# Solar_Charge_Controller.net
KiCad netlist of a schematic drawn in EAGLE
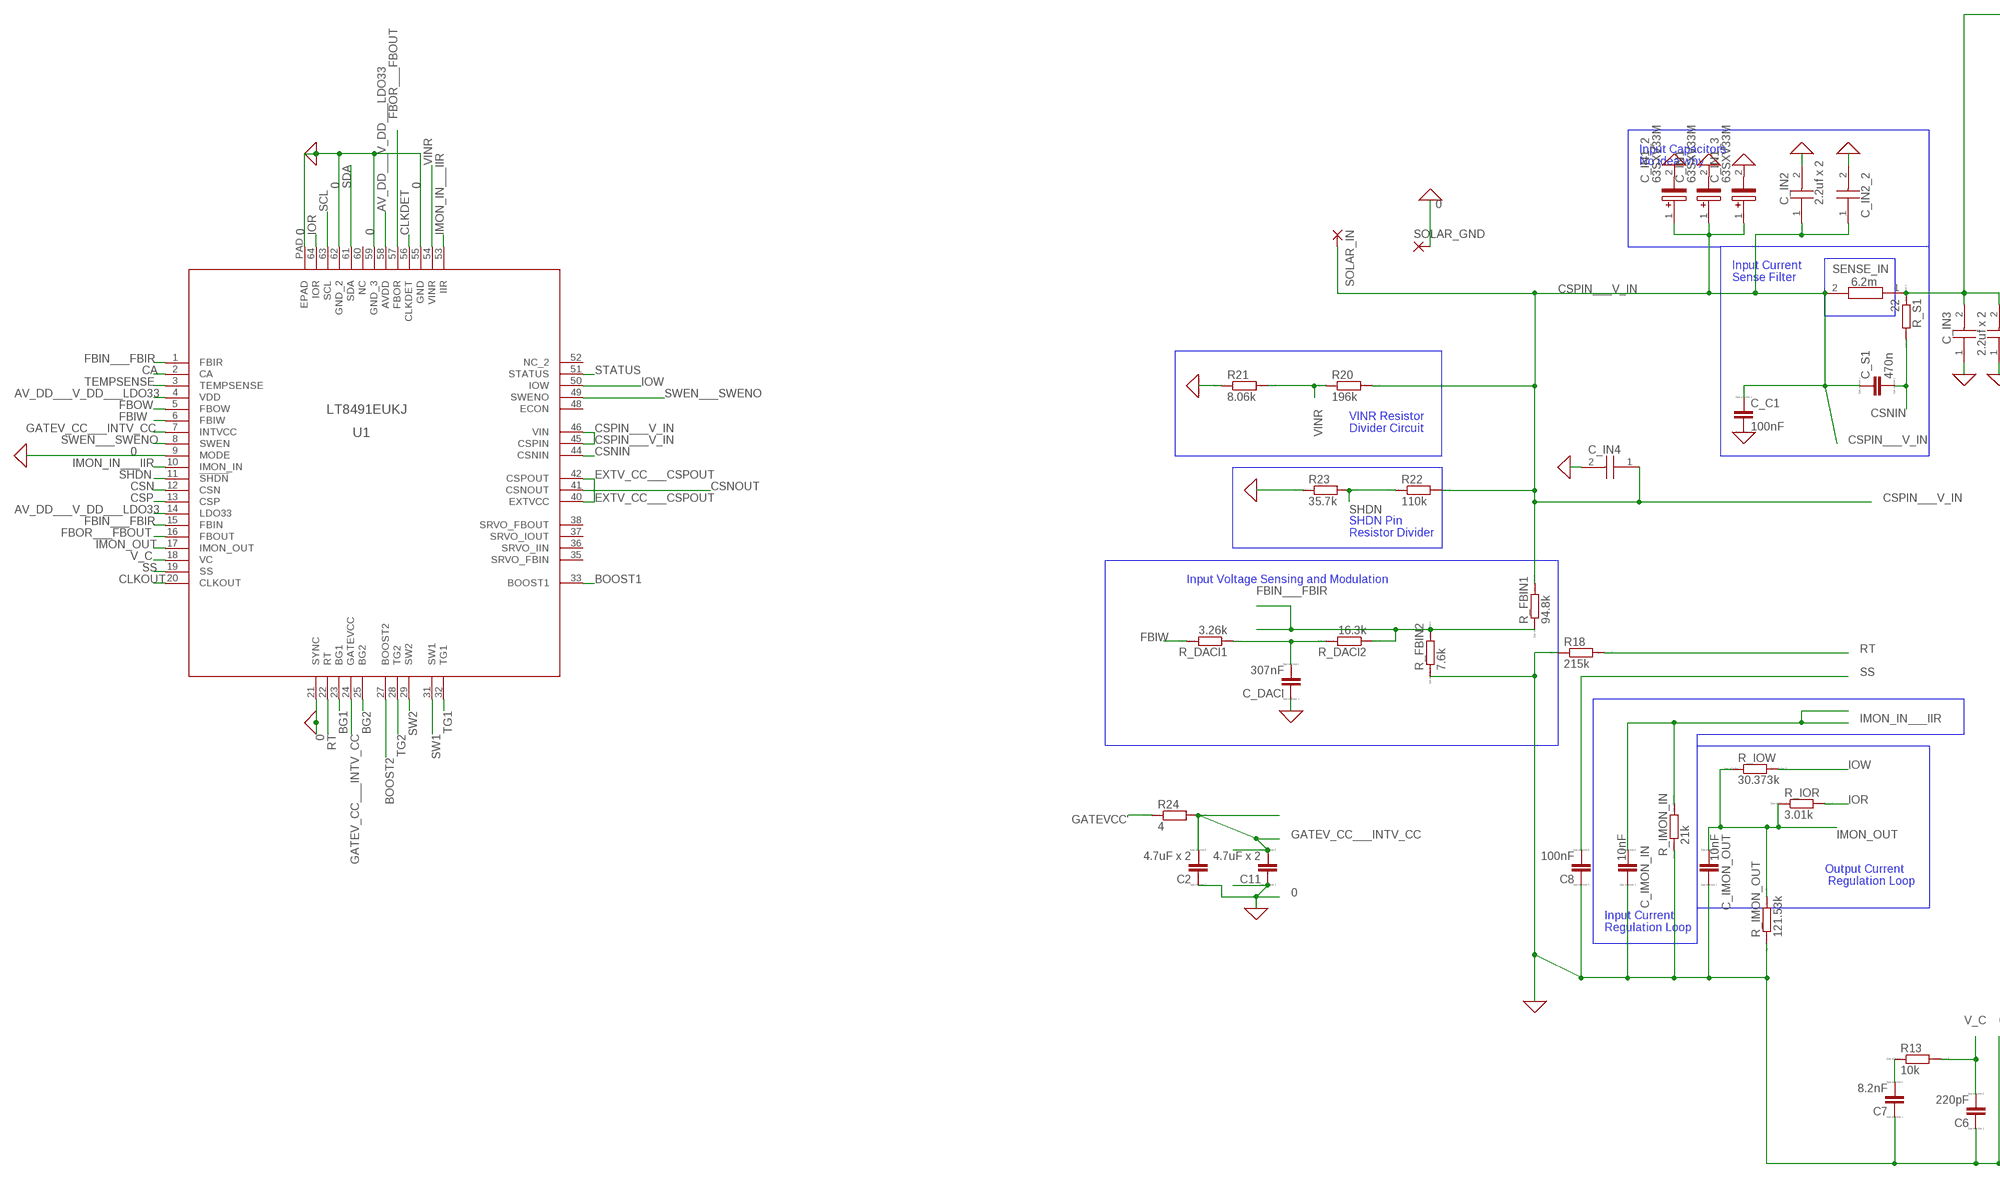
[diagram p0: schematic, sheet 1, part 1 of 2]
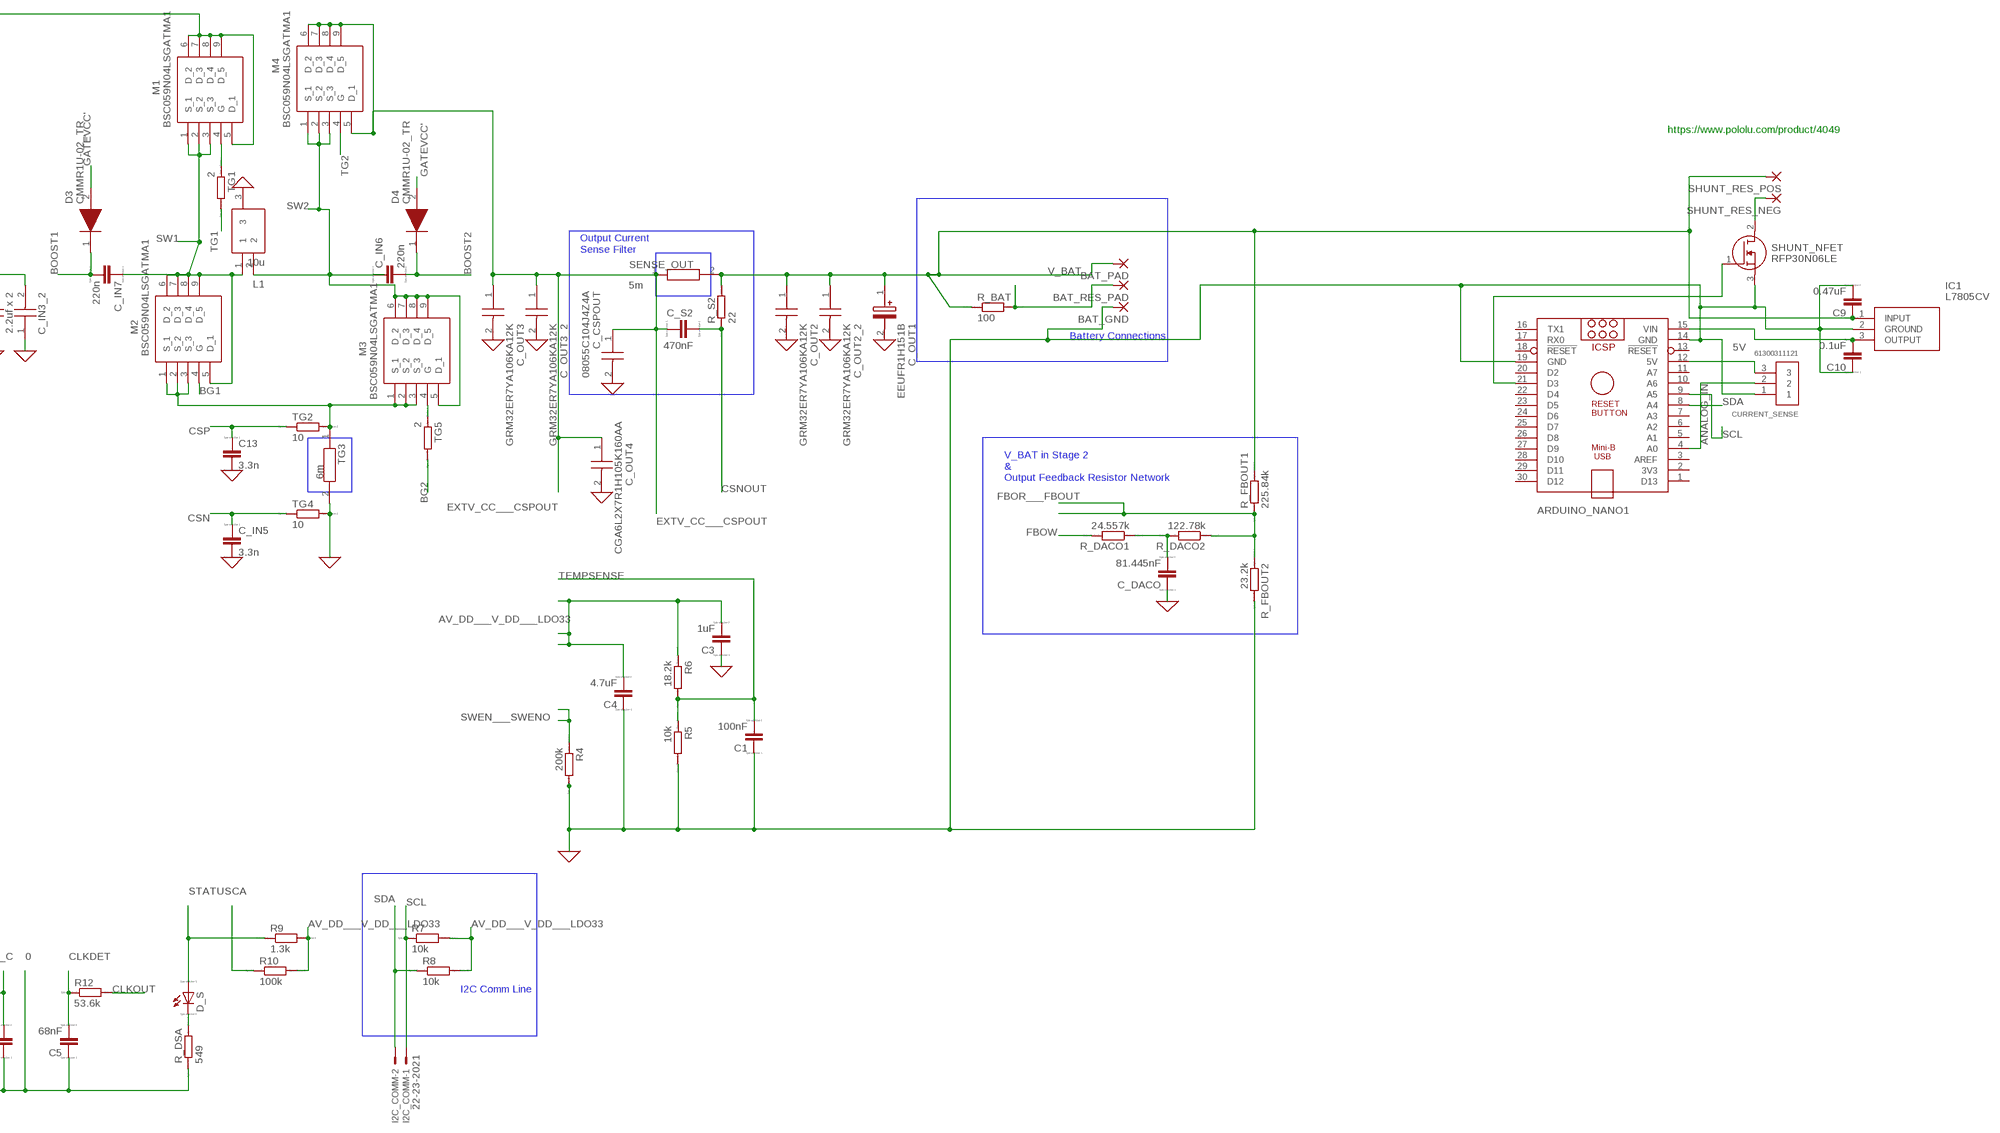
[diagram p1: schematic, sheet 1, part 2 of 2]

(export (version "E")
  (design (tool "Eeschema 10.0.6"))
  (components
    (comp (ref "ARDUINO_NANO1")
      (value "ARDUINO_NANO")
      (footprint "eagle-import:ARDUINO_NANO")
      (libsource (lib "eagle-import") (part "ARDUINO_NANO"))
    )
    (comp (ref "BAT_GND")
      (value "SMD5")
      (footprint "eagle-import:SMD2,54-5,08")
      (libsource (lib "eagle-import") (part "SMD5"))
    )
    (comp (ref "BAT_PAD")
      (value "SMD5")
      (footprint "eagle-import:SMD2,54-5,08")
      (libsource (lib "eagle-import") (part "SMD5"))
    )
    (comp (ref "BAT_RES_PAD")
      (value "SMD5")
      (footprint "eagle-import:SMD2,54-5,08")
      (libsource (lib "eagle-import") (part "SMD5"))
    )
    (comp (ref "C1")
      (value "100nF")
      (footprint "eagle-import:C1206")
      (libsource (lib "eagle-import") (part "CC1206"))
    )
    (comp (ref "C2")
      (value "4.7uF x 2")
      (footprint "eagle-import:C1206")
      (libsource (lib "eagle-import") (part "CC1206"))
    )
    (comp (ref "C3")
      (value "1uF")
      (footprint "eagle-import:C1206")
      (libsource (lib "eagle-import") (part "CC1206"))
    )
    (comp (ref "C4")
      (value "4.7uF")
      (footprint "eagle-import:C1206")
      (libsource (lib "eagle-import") (part "CC1206"))
    )
    (comp (ref "C5")
      (value "68nF")
      (footprint "eagle-import:C0603")
      (libsource (lib "eagle-import") (part "CC0603"))
    )
    (comp (ref "C6")
      (value "220pF")
      (footprint "eagle-import:C1206")
      (libsource (lib "eagle-import") (part "CC1206"))
    )
    (comp (ref "C7")
      (value "8.2nF")
      (footprint "eagle-import:C1206")
      (libsource (lib "eagle-import") (part "CC1206"))
    )
    (comp (ref "C8")
      (value "100nF")
      (footprint "eagle-import:C1206")
      (libsource (lib "eagle-import") (part "CC1206"))
    )
    (comp (ref "C9")
      (value "0.47uF")
      (footprint "eagle-import:C1206")
      (libsource (lib "eagle-import") (part "CC1206"))
    )
    (comp (ref "C10")
      (value "0.1uF")
      (footprint "eagle-import:C1206")
      (libsource (lib "eagle-import") (part "CC1206"))
    )
    (comp (ref "C11")
      (value "4.7uF x 2")
      (footprint "eagle-import:C1206")
      (libsource (lib "eagle-import") (part "CC1206"))
    )
    (comp (ref "C13")
      (value "3.3n")
      (footprint "eagle-import:C1206")
      (libsource (lib "eagle-import") (part "CC1206"))
    )
    (comp (ref "CURRENT_SENSE")
      (value "61300311121")
      (footprint "eagle-import:61300311121")
      (fields
        (field (name "DIGI_KEY_PART_NUMBER") "732-5316-ND")
        (field (name "MANUFACTURER") "Wurth Electronics Inc.")
        (field (name "CREATED_BY") "PCBLayout.com")
      )
      (libsource (lib "eagle-import") (part "61300311121"))
    )
    (comp (ref "C_C1")
      (value "100nF")
      (footprint "eagle-import:C1206")
      (libsource (lib "eagle-import") (part "CC1206"))
    )
    (comp (ref "C_CSPOUT")
      (value "08055C104J4Z4A")
      (footprint "eagle-import:CAPC2012X127N")
      (fields (field (name "MOUSER_PART_NUMBER") "581-08055C104J4Z4A"))
      (libsource (lib "eagle-import") (part "08055C104J4Z4A"))
    )
    (comp (ref "C_DACI")
      (value "307nF")
      (footprint "eagle-import:C1206")
      (libsource (lib "eagle-import") (part "CC1206"))
    )
    (comp (ref "C_DACO")
      (value "81.445nF")
      (footprint "eagle-import:C1206")
      (libsource (lib "eagle-import") (part "CC1206"))
    )
    (comp (ref "C_IMON_IN")
      (value "10nF")
      (footprint "eagle-import:C1206")
      (libsource (lib "eagle-import") (part "CC1206"))
    )
    (comp (ref "C_IMON_OUT")
      (value "10nF")
      (footprint "eagle-import:C1206")
      (libsource (lib "eagle-import") (part "CC1206"))
    )
    (comp (ref "C_IN1")
      (value "63SXV33M")
      (footprint "eagle-import:CAPAE830X1200N")
      (fields (field (name "MOUSER_PART_NUMBER") "667-63SXV33M"))
      (libsource (lib "eagle-import") (part "63SXV33M"))
    )
    (comp (ref "C_IN1_2")
      (value "63SXV33M")
      (footprint "eagle-import:CAPAE830X1200N")
      (fields (field (name "MOUSER_PART_NUMBER") "667-63SXV33M"))
      (libsource (lib "eagle-import") (part "63SXV33M"))
    )
    (comp (ref "C_IN1_3")
      (value "63SXV33M")
      (footprint "eagle-import:CAPAE830X1200N")
      (fields (field (name "MOUSER_PART_NUMBER") "667-63SXV33M"))
      (libsource (lib "eagle-import") (part "63SXV33M"))
    )
    (comp (ref "C_IN2")
      (value "2.2uf x 2")
      (footprint "eagle-import:CAPC3325X279N")
      (fields
        (field (name "ARROW_PART_NUMBER") "12101C225KAT2A")
        (field (name "MOUSER_PART_NUMBER") "581-12101C225KAT2A")
      )
      (libsource (lib "eagle-import") (part "12101C225KAT2A"))
    )
    (comp (ref "C_IN2_2")
      (value "2.2uf x 2")
      (footprint "eagle-import:CAPC3325X279N")
      (fields
        (field (name "ARROW_PART_NUMBER") "12101C225KAT2A")
        (field (name "MOUSER_PART_NUMBER") "581-12101C225KAT2A")
      )
      (libsource (lib "eagle-import") (part "12101C225KAT2A"))
    )
    (comp (ref "C_IN3")
      (value "2.2uf x 2")
      (footprint "eagle-import:CAPC3325X279N")
      (fields
        (field (name "ARROW_PART_NUMBER") "12101C225KAT2A")
        (field (name "MOUSER_PART_NUMBER") "581-12101C225KAT2A")
      )
      (libsource (lib "eagle-import") (part "12101C225KAT2A"))
    )
    (comp (ref "C_IN3_2")
      (value "2.2uf x 2")
      (footprint "eagle-import:CAPC3325X279N")
      (fields
        (field (name "ARROW_PART_NUMBER") "12101C225KAT2A")
        (field (name "MOUSER_PART_NUMBER") "581-12101C225KAT2A")
      )
      (libsource (lib "eagle-import") (part "12101C225KAT2A"))
    )
    (comp (ref "C_IN4")
      (value "2.2uf")
      (footprint "eagle-import:CAPC3325X279N")
      (fields
        (field (name "ARROW_PART_NUMBER") "12101C225KAT2A")
        (field (name "MOUSER_PART_NUMBER") "581-12101C225KAT2A")
      )
      (libsource (lib "eagle-import") (part "12101C225KAT2A"))
    )
    (comp (ref "C_IN5")
      (value "3.3n")
      (footprint "eagle-import:C1206")
      (libsource (lib "eagle-import") (part "CC1206"))
    )
    (comp (ref "C_IN6")
      (value "220n")
      (footprint "eagle-import:C1206")
      (libsource (lib "eagle-import") (part "CC1206"))
    )
    (comp (ref "C_IN7")
      (value "220n")
      (footprint "eagle-import:C1206")
      (libsource (lib "eagle-import") (part "CC1206"))
    )
    (comp (ref "C_OUT1")
      (value "EEUFR1H151B")
      (footprint "eagle-import:CAPPRD500W65D1000H1400")
      (libsource (lib "eagle-import") (part "EEUFR1H151B"))
    )
    (comp (ref "C_OUT2")
      (value "GRM32ER7YA106KA12K")
      (footprint "eagle-import:CAPC3225X270N")
      (fields (field (name "MOUSER_PART_NUMBER") "81-GRM32ER7YA106KA2K"))
      (libsource (lib "eagle-import") (part "GRM32ER7YA106KA12K"))
    )
    (comp (ref "C_OUT2_2")
      (value "GRM32ER7YA106KA12K")
      (footprint "eagle-import:CAPC3225X270N")
      (fields (field (name "MOUSER_PART_NUMBER") "81-GRM32ER7YA106KA2K"))
      (libsource (lib "eagle-import") (part "GRM32ER7YA106KA12K"))
    )
    (comp (ref "C_OUT3")
      (value "GRM32ER7YA106KA12K")
      (footprint "eagle-import:CAPC3225X270N")
      (fields (field (name "MOUSER_PART_NUMBER") "81-GRM32ER7YA106KA2K"))
      (libsource (lib "eagle-import") (part "GRM32ER7YA106KA12K"))
    )
    (comp (ref "C_OUT3_2")
      (value "GRM32ER7YA106KA12K")
      (footprint "eagle-import:CAPC3225X270N")
      (fields (field (name "MOUSER_PART_NUMBER") "81-GRM32ER7YA106KA2K"))
      (libsource (lib "eagle-import") (part "GRM32ER7YA106KA12K"))
    )
    (comp (ref "C_OUT4")
      (value "CGA6L2X7R1H105K160AA")
      (footprint "eagle-import:CAPC3225X280N")
      (fields (field (name "MOUSER_PART_NUMBER") "810-CGA6L2X7R1H105K"))
      (libsource (lib "eagle-import") (part "CGA6L2X7R1H105K160AA"))
    )
    (comp (ref "C_S1")
      (value "470n")
      (footprint "eagle-import:C1206")
      (libsource (lib "eagle-import") (part "CC1206"))
    )
    (comp (ref "C_S2")
      (value "470nF")
      (footprint "eagle-import:C1206")
      (libsource (lib "eagle-import") (part "CC1206"))
    )
    (comp (ref "D3")
      (value "CMMR1U-02_TR")
      (footprint "eagle-import:SODFL3818X108N")
      (fields
        (field (name "MANUFACTURER_PART_NUMBER") "CMMR1U-02 TR")
        (field (name "MOUSER_PART_NUMBER") "610-CMMR1U-02")
      )
      (libsource (lib "eagle-import") (part "CMMR1U-02_TR"))
    )
    (comp (ref "D4")
      (value "CMMR1U-02_TR")
      (footprint "eagle-import:SODFL3818X108N")
      (fields
        (field (name "MANUFACTURER_PART_NUMBER") "CMMR1U-02 TR")
        (field (name "MOUSER_PART_NUMBER") "610-CMMR1U-02")
      )
      (libsource (lib "eagle-import") (part "CMMR1U-02_TR"))
    )
    (comp (ref "D_S")
      (value "LED_E")
      (footprint "eagle-import:LED_1206")
      (libsource (lib "eagle-import") (part "LED_E"))
    )
    (comp (ref "I2C_COMM")
      (value "22-23-2021")
      (footprint "eagle-import:22-23-2021")
      (fields (field (name "MF") "MOLEX"))
      (libsource (lib "eagle-import") (part "22-23-2021"))
    )
    (comp (ref "IC1")
      (value "L7805CV")
      (footprint "eagle-import:TO255P460X1020X2008-3P")
      (fields (field (name "MOUSER_PART_NUMBER") "511-L7805CV"))
      (libsource (lib "eagle-import") (part "L7805CV"))
    )
    (comp (ref "L1")
      (value "10u")
      (footprint "eagle-import:SER2900")
      (fields
        (field (name "MANUFACTURER_PART_NUMBER") "SER2915H-103KL")
        (field (name "MOUSER_PART_NUMBER") "994-SER2915H-103KL")
      )
      (libsource (lib "eagle-import") (part "SER2915H-103KL"))
    )
    (comp (ref "M1")
      (value "BSC059N04LSGATMA1")
      (footprint "eagle-import:BSC080N03LSG")
      (fields (field (name "MOUSER_PART_NUMBER") "726-BSC059N04LSGATMA"))
      (libsource (lib "eagle-import") (part "BSC059N04LSGATMA1"))
    )
    (comp (ref "M2")
      (value "BSC059N04LSGATMA1")
      (footprint "eagle-import:BSC080N03LSG")
      (fields (field (name "MOUSER_PART_NUMBER") "726-BSC059N04LSGATMA"))
      (libsource (lib "eagle-import") (part "BSC059N04LSGATMA1"))
    )
    (comp (ref "M3")
      (value "BSC059N04LSGATMA1")
      (footprint "eagle-import:BSC080N03LSG")
      (fields (field (name "MOUSER_PART_NUMBER") "726-BSC059N04LSGATMA"))
      (libsource (lib "eagle-import") (part "BSC059N04LSGATMA1"))
    )
    (comp (ref "M4")
      (value "BSC059N04LSGATMA1")
      (footprint "eagle-import:BSC080N03LSG")
      (fields (field (name "MOUSER_PART_NUMBER") "726-BSC059N04LSGATMA"))
      (libsource (lib "eagle-import") (part "BSC059N04LSGATMA1"))
    )
    (comp (ref "R4")
      (value "200k")
      (footprint "eagle-import:R1206")
      (libsource (lib "eagle-import") (part "RR1206"))
    )
    (comp (ref "R5")
      (value "10k")
      (footprint "eagle-import:R1206")
      (libsource (lib "eagle-import") (part "RR1206"))
    )
    (comp (ref "R6")
      (value "18.2k")
      (footprint "eagle-import:R1206")
      (libsource (lib "eagle-import") (part "RR1206"))
    )
    (comp (ref "R7")
      (value "10k")
      (footprint "eagle-import:R1206")
      (libsource (lib "eagle-import") (part "RR1206"))
    )
    (comp (ref "R8")
      (value "10k")
      (footprint "eagle-import:R1206")
      (libsource (lib "eagle-import") (part "RR1206"))
    )
    (comp (ref "R9")
      (value "1.3k")
      (footprint "eagle-import:R1206")
      (libsource (lib "eagle-import") (part "RR1206"))
    )
    (comp (ref "R10")
      (value "100k")
      (footprint "eagle-import:R1206")
      (libsource (lib "eagle-import") (part "RR1206"))
    )
    (comp (ref "R12")
      (value "53.6k")
      (footprint "eagle-import:R1206")
      (libsource (lib "eagle-import") (part "RR1206"))
    )
    (comp (ref "R13")
      (value "10k")
      (footprint "eagle-import:R1206")
      (libsource (lib "eagle-import") (part "RR1206"))
    )
    (comp (ref "R18")
      (value "215k")
      (footprint "eagle-import:R1206")
      (libsource (lib "eagle-import") (part "RR1206"))
    )
    (comp (ref "R20")
      (value "196k")
      (footprint "eagle-import:R1206")
      (libsource (lib "eagle-import") (part "RR1206"))
    )
    (comp (ref "R21")
      (value "8.06k")
      (footprint "eagle-import:R1206")
      (libsource (lib "eagle-import") (part "RR1206"))
    )
    (comp (ref "R22")
      (value "110k")
      (footprint "eagle-import:R1206")
      (libsource (lib "eagle-import") (part "RR1206"))
    )
    (comp (ref "R23")
      (value "35.7k")
      (footprint "eagle-import:R1206")
      (libsource (lib "eagle-import") (part "RR1206"))
    )
    (comp (ref "R24")
      (value "4")
      (footprint "eagle-import:R1206")
      (libsource (lib "eagle-import") (part "RR1206"))
    )
    (comp (ref "R_BAT")
      (value "100")
      (footprint "eagle-import:R1206")
      (libsource (lib "eagle-import") (part "RR1206"))
    )
    (comp (ref "R_DACI1")
      (value "3.26k")
      (footprint "eagle-import:R1206")
      (libsource (lib "eagle-import") (part "RR1206"))
    )
    (comp (ref "R_DACI2")
      (value "16.3k")
      (footprint "eagle-import:R1206")
      (libsource (lib "eagle-import") (part "RR1206"))
    )
    (comp (ref "R_DACO1")
      (value "24.557k")
      (footprint "eagle-import:R1206")
      (libsource (lib "eagle-import") (part "RR1206"))
    )
    (comp (ref "R_DACO2")
      (value "122.78k")
      (footprint "eagle-import:R1206")
      (libsource (lib "eagle-import") (part "RR1206"))
    )
    (comp (ref "R_DSA")
      (value "549")
      (footprint "eagle-import:R1206")
      (libsource (lib "eagle-import") (part "RR1206"))
    )
    (comp (ref "R_FBIN1")
      (value "94.8k")
      (footprint "eagle-import:R1206")
      (libsource (lib "eagle-import") (part "RR1206"))
    )
    (comp (ref "R_FBIN2")
      (value "7.6k")
      (footprint "eagle-import:R1206")
      (libsource (lib "eagle-import") (part "RR1206"))
    )
    (comp (ref "R_FBOUT1")
      (value "225.84k")
      (footprint "eagle-import:R1206")
      (libsource (lib "eagle-import") (part "RR1206"))
    )
    (comp (ref "R_FBOUT2")
      (value "23.2k")
      (footprint "eagle-import:R1206")
      (libsource (lib "eagle-import") (part "RR1206"))
    )
    (comp (ref "R_IMON_IN")
      (value "21k")
      (footprint "eagle-import:R1206")
      (libsource (lib "eagle-import") (part "RR1206"))
    )
    (comp (ref "R_IMON_OUT")
      (value "121.53k")
      (footprint "eagle-import:R1206")
      (libsource (lib "eagle-import") (part "RR1206"))
    )
    (comp (ref "R_IOR")
      (value "3.01k")
      (footprint "eagle-import:R1206")
      (libsource (lib "eagle-import") (part "RR1206"))
    )
    (comp (ref "R_IOW")
      (value "30.373k")
      (footprint "eagle-import:R1206")
      (libsource (lib "eagle-import") (part "RR1206"))
    )
    (comp (ref "R_S1")
      (value "22")
      (footprint "eagle-import:R1206")
      (libsource (lib "eagle-import") (part "RR1206"))
    )
    (comp (ref "R_S2")
      (value "22")
      (footprint "eagle-import:R1206")
      (libsource (lib "eagle-import") (part "RR1206"))
    )
    (comp (ref "SENSE_IN")
      (value "6.2m")
      (footprint "eagle-import:RESC2012X80N")
      (fields (field (name "MANUFACTURER_PART_NUMBER") "ERJ6LWFR006V"))
      (libsource (lib "eagle-import") (part "ERJ6LWFR006V"))
    )
    (comp (ref "SENSE_OUT")
      (value "5m")
      (footprint "eagle-import:RESC3216X89N")
      (fields
        (field (name "MANUFACTURER_PART_NUMBER") "ERJ-MP2MF5M0U")
        (field (name "MOUSER_PART_NUMBER") "667-ERJ-MP2MF5M0U")
      )
      (libsource (lib "eagle-import") (part "ERJ-MP2MF5M0U"))
    )
    (comp (ref "SHUNT_NFET")
      (value "RFP30N06LE")
      (footprint "eagle-import:TO254P470X1016X2019-3P")
      (fields (field (name "MOUSER_PART_NUMBER") "512-RFP30N06LE"))
      (libsource (lib "eagle-import") (part "RFP30N06LE"))
    )
    (comp (ref "SHUNT_RES_NEG")
      (value "SMD5")
      (footprint "eagle-import:SMD2,54-5,08")
      (libsource (lib "eagle-import") (part "SMD5"))
    )
    (comp (ref "SHUNT_RES_POS")
      (value "SMD5")
      (footprint "eagle-import:SMD2,54-5,08")
      (libsource (lib "eagle-import") (part "SMD5"))
    )
    (comp (ref "SOLAR_GND")
      (value "SMD5")
      (footprint "eagle-import:SMD2,54-5,08")
      (libsource (lib "eagle-import") (part "SMD5"))
    )
    (comp (ref "SOLAR_IN")
      (value "SMD5")
      (footprint "eagle-import:SMD2,54-5,08")
      (libsource (lib "eagle-import") (part "SMD5"))
    )
    (comp (ref "TG1")
      (value "2")
      (footprint "eagle-import:R1206")
      (libsource (lib "eagle-import") (part "RR1206"))
    )
    (comp (ref "TG2")
      (value "10")
      (footprint "eagle-import:R1206")
      (libsource (lib "eagle-import") (part "RR1206"))
    )
    (comp (ref "TG3")
      (value "6m")
      (footprint "eagle-import:RESC2012X80N")
      (fields (field (name "MANUFACTURER_PART_NUMBER") "ERJ6LWFR006V"))
      (libsource (lib "eagle-import") (part "ERJ6LWFR006V"))
    )
    (comp (ref "TG4")
      (value "10")
      (footprint "eagle-import:R1206")
      (libsource (lib "eagle-import") (part "RR1206"))
    )
    (comp (ref "TG5")
      (value "2")
      (footprint "eagle-import:R1206")
      (libsource (lib "eagle-import") (part "RR1206"))
    )
    (comp (ref "U1")
      (value "LT8491EUKJ")
      (footprint "eagle-import:QFN64(58)-UKJ-REV0_ADI")
      (fields (field (name "COPYRIGHT") "Copyright (C) 2018 Accelerated Designs. All rights reserved"))
      (libsource (lib "eagle-import") (part "LT8491EUKJ"))
    )
  )
  (nets
    (net (code "1") (name "/5V") (class "Default")
      (node (ref "ARDUINO_NANO1") (pin "12") (pinfunction "5V_12") (pintype "power_in"))
      (node (ref "CURRENT_SENSE") (pin "3") (pinfunction "3_3") (pintype "passive"))
    )
    (net (code "2") (name "/ANALOG_IN") (class "Default")
      (node (ref "ARDUINO_NANO1") (pin "4") (pinfunction "A0_4") (pintype "bidirectional"))
      (node (ref "CURRENT_SENSE") (pin "2") (pinfunction "2_2") (pintype "passive"))
    )
    (net (code "3") (name "/AV_DD___V_DD___LDO33") (class "Default")
      (node (ref "C3") (pin "2") (pinfunction "2_2") (pintype "passive"))
      (node (ref "C4") (pin "2") (pinfunction "2_2") (pintype "passive"))
      (node (ref "R10") (pin "2") (pinfunction "2_2") (pintype "passive"))
      (node (ref "R6") (pin "1") (pinfunction "1_1") (pintype "passive"))
      (node (ref "R7") (pin "2") (pinfunction "2_2") (pintype "passive"))
      (node (ref "R8") (pin "2") (pinfunction "2_2") (pintype "passive"))
      (node (ref "R9") (pin "2") (pinfunction "2_2") (pintype "passive"))
      (node (ref "U1") (pin "14") (pinfunction "LDO33_14") (pintype "passive"))
      (node (ref "U1") (pin "4") (pinfunction "VDD_4") (pintype "passive"))
      (node (ref "U1") (pin "58") (pinfunction "AVDD_58") (pintype "passive"))
    )
    (net (code "4") (name "/BG1") (class "Default")
      (node (ref "M2") (pin "4") (pinfunction "G_4") (pintype "bidirectional"))
      (node (ref "U1") (pin "23") (pinfunction "BG1_23") (pintype "passive"))
    )
    (net (code "5") (name "/BG2") (class "Default")
      (node (ref "TG5") (pin "2") (pinfunction "2_2") (pintype "passive"))
      (node (ref "U1") (pin "25") (pinfunction "BG2_25") (pintype "passive"))
    )
    (net (code "6") (name "/BOOST1") (class "Default")
      (node (ref "C_IN7") (pin "2") (pinfunction "2_2") (pintype "passive"))
      (node (ref "D3") (pin "1") (pinfunction "K_1") (pintype "bidirectional"))
      (node (ref "U1") (pin "33") (pinfunction "BOOST1_33") (pintype "passive"))
    )
    (net (code "7") (name "/BOOST2") (class "Default")
      (node (ref "C_IN6") (pin "2") (pinfunction "2_2") (pintype "passive"))
      (node (ref "D4") (pin "1") (pinfunction "K_1") (pintype "bidirectional"))
      (node (ref "U1") (pin "27") (pinfunction "BOOST2_27") (pintype "passive"))
    )
    (net (code "8") (name "/CA") (class "Default")
      (node (ref "R10") (pin "1") (pinfunction "1_1") (pintype "passive"))
      (node (ref "U1") (pin "2") (pinfunction "CA_2") (pintype "passive"))
    )
    (net (code "9") (name "/CLKDET") (class "Default")
      (node (ref "C5") (pin "2") (pinfunction "2_2") (pintype "passive"))
      (node (ref "R12") (pin "1") (pinfunction "1_1") (pintype "passive"))
      (node (ref "U1") (pin "56") (pinfunction "CLKDET_56") (pintype "passive"))
    )
    (net (code "10") (name "/CLKOUT") (class "Default")
      (node (ref "R12") (pin "2") (pinfunction "2_2") (pintype "passive"))
      (node (ref "U1") (pin "20") (pinfunction "CLKOUT_20") (pintype "passive"))
    )
    (net (code "11") (name "/CSN") (class "Default")
      (node (ref "C_IN5") (pin "1") (pinfunction "1_1") (pintype "passive"))
      (node (ref "TG4") (pin "1") (pinfunction "1_1") (pintype "passive"))
      (node (ref "U1") (pin "12") (pinfunction "CSN_12") (pintype "passive"))
    )
    (net (code "12") (name "/CSNIN") (class "Default")
      (node (ref "C_S1") (pin "2") (pinfunction "2_2") (pintype "passive"))
      (node (ref "R_S1") (pin "2") (pinfunction "2_2") (pintype "passive"))
      (node (ref "U1") (pin "44") (pinfunction "CSNIN_44") (pintype "passive"))
    )
    (net (code "13") (name "/CSNOUT") (class "Default")
      (node (ref "C_S2") (pin "2") (pinfunction "2_2") (pintype "passive"))
      (node (ref "R_S2") (pin "1") (pinfunction "1_1") (pintype "passive"))
      (node (ref "U1") (pin "41") (pinfunction "CSNOUT_41") (pintype "passive"))
    )
    (net (code "14") (name "/CSP") (class "Default")
      (node (ref "C13") (pin "1") (pinfunction "1_1") (pintype "passive"))
      (node (ref "TG2") (pin "1") (pinfunction "1_1") (pintype "passive"))
      (node (ref "U1") (pin "13") (pinfunction "CSP_13") (pintype "passive"))
    )
    (net (code "15") (name "/CSPIN___V_IN") (class "Default")
      (node (ref "C_C1") (pin "1") (pinfunction "1_1") (pintype "passive"))
      (node (ref "C_IN1") (pin "1") (pinfunction "+_1") (pintype "bidirectional"))
      (node (ref "C_IN1_2") (pin "1") (pinfunction "+_1") (pintype "bidirectional"))
      (node (ref "C_IN1_3") (pin "1") (pinfunction "+_1") (pintype "bidirectional"))
      (node (ref "C_IN2") (pin "1") (pinfunction "1_1") (pintype "bidirectional"))
      (node (ref "C_IN2_2") (pin "1") (pinfunction "1_1") (pintype "bidirectional"))
      (node (ref "C_IN4") (pin "1") (pinfunction "1_1") (pintype "bidirectional"))
      (node (ref "C_S1") (pin "1") (pinfunction "1_1") (pintype "passive"))
      (node (ref "R20") (pin "2") (pinfunction "2_2") (pintype "passive"))
      (node (ref "R22") (pin "2") (pinfunction "2_2") (pintype "passive"))
      (node (ref "R_FBIN1") (pin "2") (pinfunction "2_2") (pintype "passive"))
      (node (ref "SENSE_IN") (pin "2") (pinfunction "2_2") (pintype "bidirectional"))
      (node (ref "SOLAR_IN") (pin "1") (pinfunction "P_1") (pintype "passive"))
      (node (ref "U1") (pin "45") (pinfunction "CSPIN_45") (pintype "passive"))
      (node (ref "U1") (pin "46") (pinfunction "VIN_46") (pintype "passive"))
    )
    (net (code "16") (name "/EXTV_CC___CSPOUT") (class "Default")
      (node (ref "C_CSPOUT") (pin "1") (pinfunction "1_1") (pintype "bidirectional"))
      (node (ref "C_OUT3") (pin "1") (pinfunction "1_1") (pintype "bidirectional"))
      (node (ref "C_OUT3_2") (pin "1") (pinfunction "1_1") (pintype "bidirectional"))
      (node (ref "C_OUT4") (pin "1") (pinfunction "1_1") (pintype "bidirectional"))
      (node (ref "C_S2") (pin "1") (pinfunction "1_1") (pintype "passive"))
      (node (ref "M4") (pin "5") (pinfunction "D_1_5") (pintype "bidirectional"))
      (node (ref "M4") (pin "6") (pinfunction "D_2_6") (pintype "bidirectional"))
      (node (ref "M4") (pin "7") (pinfunction "D_3_7") (pintype "bidirectional"))
      (node (ref "M4") (pin "8") (pinfunction "D_4_8") (pintype "bidirectional"))
      (node (ref "M4") (pin "9") (pinfunction "D_5_9") (pintype "bidirectional"))
      (node (ref "SENSE_OUT") (pin "1") (pinfunction "1_1") (pintype "bidirectional"))
      (node (ref "U1") (pin "40") (pinfunction "EXTVCC_40") (pintype "passive"))
      (node (ref "U1") (pin "42") (pinfunction "CSPOUT_42") (pintype "passive"))
    )
    (net (code "17") (name "/FBIN___FBIR") (class "Default")
      (node (ref "R_DACI2") (pin "1") (pinfunction "1_1") (pintype "passive"))
      (node (ref "R_FBIN1") (pin "1") (pinfunction "1_1") (pintype "passive"))
      (node (ref "R_FBIN2") (pin "2") (pinfunction "2_2") (pintype "passive"))
      (node (ref "U1") (pin "1") (pinfunction "FBIR_1") (pintype "passive"))
      (node (ref "U1") (pin "15") (pinfunction "FBIN_15") (pintype "passive"))
    )
    (net (code "18") (name "/FBIW") (class "Default")
      (node (ref "R_DACI1") (pin "2") (pinfunction "2_2") (pintype "passive"))
      (node (ref "U1") (pin "6") (pinfunction "FBIW_6") (pintype "passive"))
    )
    (net (code "19") (name "/FBOR___FBOUT") (class "Default")
      (node (ref "R_DACO2") (pin "1") (pinfunction "1_1") (pintype "passive"))
      (node (ref "R_FBOUT1") (pin "1") (pinfunction "1_1") (pintype "passive"))
      (node (ref "R_FBOUT2") (pin "1") (pinfunction "1_1") (pintype "passive"))
      (node (ref "U1") (pin "16") (pinfunction "FBOUT_16") (pintype "passive"))
      (node (ref "U1") (pin "57") (pinfunction "FBOR_57") (pintype "passive"))
    )
    (net (code "20") (name "/FBOW") (class "Default")
      (node (ref "R_DACO1") (pin "2") (pinfunction "2_2") (pintype "passive"))
      (node (ref "U1") (pin "5") (pinfunction "FBOW_5") (pintype "passive"))
    )
    (net (code "21") (name "/GATEVCC'") (class "Default")
      (node (ref "D3") (pin "2") (pinfunction "A_2") (pintype "bidirectional"))
      (node (ref "D4") (pin "2") (pinfunction "A_2") (pintype "bidirectional"))
      (node (ref "R24") (pin "1") (pinfunction "1_1") (pintype "passive"))
    )
    (net (code "22") (name "/GATEV_CC___INTV_CC") (class "Default")
      (node (ref "C11") (pin "2") (pinfunction "2_2") (pintype "passive"))
      (node (ref "C2") (pin "2") (pinfunction "2_2") (pintype "passive"))
      (node (ref "R24") (pin "2") (pinfunction "2_2") (pintype "passive"))
      (node (ref "U1") (pin "24") (pinfunction "GATEVCC_24") (pintype "passive"))
      (node (ref "U1") (pin "7") (pinfunction "INTVCC_7") (pintype "passive"))
    )
    (net (code "23") (name "/IMON_IN___IIR") (class "Default")
      (node (ref "C_IMON_IN") (pin "2") (pinfunction "2_2") (pintype "passive"))
      (node (ref "R_IMON_IN") (pin "2") (pinfunction "2_2") (pintype "passive"))
      (node (ref "U1") (pin "10") (pinfunction "IMON_IN_10") (pintype "passive"))
      (node (ref "U1") (pin "53") (pinfunction "IIR_53") (pintype "passive"))
    )
    (net (code "24") (name "/IMON_OUT") (class "Default")
      (node (ref "C_IMON_OUT") (pin "2") (pinfunction "2_2") (pintype "passive"))
      (node (ref "R_IMON_OUT") (pin "2") (pinfunction "2_2") (pintype "passive"))
      (node (ref "R_IOR") (pin "1") (pinfunction "1_1") (pintype "passive"))
      (node (ref "R_IOW") (pin "1") (pinfunction "1_1") (pintype "passive"))
      (node (ref "U1") (pin "17") (pinfunction "IMON_OUT_17") (pintype "passive"))
    )
    (net (code "25") (name "/IOR") (class "Default")
      (node (ref "R_IOR") (pin "2") (pinfunction "2_2") (pintype "passive"))
      (node (ref "U1") (pin "64") (pinfunction "IOR_64") (pintype "passive"))
    )
    (net (code "26") (name "/IOW") (class "Default")
      (node (ref "R_IOW") (pin "2") (pinfunction "2_2") (pintype "passive"))
      (node (ref "U1") (pin "50") (pinfunction "IOW_50") (pintype "passive"))
    )
    (net (code "27") (name "/RT") (class "Default")
      (node (ref "R18") (pin "2") (pinfunction "2_2") (pintype "passive"))
      (node (ref "U1") (pin "22") (pinfunction "RT_22") (pintype "passive"))
    )
    (net (code "28") (name "/SCL") (class "Default")
      (node (ref "ARDUINO_NANO1") (pin "9") (pinfunction "A5_9") (pintype "bidirectional"))
      (node (ref "I2C_COMM") (pin "1") (pinfunction "S_1") (pintype "passive"))
      (node (ref "R7") (pin "1") (pinfunction "1_1") (pintype "passive"))
      (node (ref "U1") (pin "63") (pinfunction "SCL_63") (pintype "passive"))
    )
    (net (code "29") (name "/SDA") (class "Default")
      (node (ref "ARDUINO_NANO1") (pin "8") (pinfunction "A4_8") (pintype "bidirectional"))
      (node (ref "I2C_COMM") (pin "2") (pinfunction "S_2") (pintype "passive"))
      (node (ref "R8") (pin "1") (pinfunction "1_1") (pintype "passive"))
      (node (ref "U1") (pin "61") (pinfunction "SDA_61") (pintype "passive"))
    )
    (net (code "30") (name "/SHDN") (class "Default")
      (node (ref "R22") (pin "1") (pinfunction "1_1") (pintype "passive"))
      (node (ref "R23") (pin "2") (pinfunction "2_2") (pintype "passive"))
      (node (ref "U1") (pin "11") (pinfunction "~{SHDN}_11") (pintype "passive"))
    )
    (net (code "31") (name "/SS") (class "Default")
      (node (ref "C8") (pin "2") (pinfunction "2_2") (pintype "passive"))
      (node (ref "U1") (pin "19") (pinfunction "SS_19") (pintype "passive"))
    )
    (net (code "32") (name "/STATUS") (class "Default")
      (node (ref "D_S") (pin "A") (pinfunction "A_A") (pintype "passive"))
      (node (ref "R9") (pin "1") (pinfunction "1_1") (pintype "passive"))
      (node (ref "U1") (pin "51") (pinfunction "STATUS_51") (pintype "passive"))
    )
    (net (code "33") (name "/SW1") (class "Default")
      (node (ref "C_IN7") (pin "1") (pinfunction "1_1") (pintype "passive"))
      (node (ref "L1") (pin "1") (pinfunction "1_1") (pintype "bidirectional"))
      (node (ref "M1") (pin "1") (pinfunction "S_1_1") (pintype "bidirectional"))
      (node (ref "M1") (pin "2") (pinfunction "S_2_2") (pintype "bidirectional"))
      (node (ref "M1") (pin "3") (pinfunction "S_3_3") (pintype "bidirectional"))
      (node (ref "M2") (pin "5") (pinfunction "D_1_5") (pintype "bidirectional"))
      (node (ref "M2") (pin "6") (pinfunction "D_2_6") (pintype "bidirectional"))
      (node (ref "M2") (pin "7") (pinfunction "D_3_7") (pintype "bidirectional"))
      (node (ref "M2") (pin "8") (pinfunction "D_4_8") (pintype "bidirectional"))
      (node (ref "M2") (pin "9") (pinfunction "D_5_9") (pintype "bidirectional"))
      (node (ref "U1") (pin "31") (pinfunction "SW1_31") (pintype "passive"))
    )
    (net (code "34") (name "/SW2") (class "Default")
      (node (ref "C_IN6") (pin "1") (pinfunction "1_1") (pintype "passive"))
      (node (ref "L1") (pin "2") (pinfunction "2_2") (pintype "bidirectional"))
      (node (ref "M3") (pin "5") (pinfunction "D_1_5") (pintype "bidirectional"))
      (node (ref "M3") (pin "6") (pinfunction "D_2_6") (pintype "bidirectional"))
      (node (ref "M3") (pin "7") (pinfunction "D_3_7") (pintype "bidirectional"))
      (node (ref "M3") (pin "8") (pinfunction "D_4_8") (pintype "bidirectional"))
      (node (ref "M3") (pin "9") (pinfunction "D_5_9") (pintype "bidirectional"))
      (node (ref "M4") (pin "1") (pinfunction "S_1_1") (pintype "bidirectional"))
      (node (ref "M4") (pin "2") (pinfunction "S_2_2") (pintype "bidirectional"))
      (node (ref "M4") (pin "3") (pinfunction "S_3_3") (pintype "bidirectional"))
      (node (ref "U1") (pin "29") (pinfunction "SW2_29") (pintype "passive"))
    )
    (net (code "35") (name "/SWEN___SWENO") (class "Default")
      (node (ref "R4") (pin "1") (pinfunction "1_1") (pintype "passive"))
      (node (ref "U1") (pin "49") (pinfunction "SWENO_49") (pintype "passive"))
      (node (ref "U1") (pin "8") (pinfunction "SWEN_8") (pintype "passive"))
    )
    (net (code "36") (name "/TEMPSENSE") (class "Default")
      (node (ref "C1") (pin "2") (pinfunction "2_2") (pintype "passive"))
      (node (ref "R5") (pin "1") (pinfunction "1_1") (pintype "passive"))
      (node (ref "R6") (pin "2") (pinfunction "2_2") (pintype "passive"))
      (node (ref "U1") (pin "3") (pinfunction "TEMPSENSE_3") (pintype "passive"))
    )
    (net (code "37") (name "/TG1") (class "Default")
      (node (ref "TG1") (pin "2") (pinfunction "2_2") (pintype "passive"))
      (node (ref "U1") (pin "32") (pinfunction "TG1_32") (pintype "passive"))
    )
    (net (code "38") (name "/TG2") (class "Default")
      (node (ref "M4") (pin "4") (pinfunction "G_4") (pintype "bidirectional"))
      (node (ref "U1") (pin "28") (pinfunction "TG2_28") (pintype "passive"))
    )
    (net (code "39") (name "/VINR") (class "Default")
      (node (ref "R20") (pin "1") (pinfunction "1_1") (pintype "passive"))
      (node (ref "R21") (pin "2") (pinfunction "2_2") (pintype "passive"))
      (node (ref "U1") (pin "54") (pinfunction "VINR_54") (pintype "passive"))
    )
    (net (code "40") (name "/V_BAT") (class "Default")
      (node (ref "BAT_PAD") (pin "1") (pinfunction "P_1") (pintype "passive"))
      (node (ref "C9") (pin "1") (pinfunction "1_1") (pintype "passive"))
      (node (ref "C_OUT1") (pin "1") (pinfunction "+_1") (pintype "bidirectional"))
      (node (ref "C_OUT2") (pin "1") (pinfunction "1_1") (pintype "bidirectional"))
      (node (ref "C_OUT2_2") (pin "1") (pinfunction "1_1") (pintype "bidirectional"))
      (node (ref "IC1") (pin "1") (pinfunction "INPUT_1") (pintype "bidirectional"))
      (node (ref "R_BAT") (pin "1") (pinfunction "1_1") (pintype "passive"))
      (node (ref "R_FBOUT1") (pin "2") (pinfunction "2_2") (pintype "passive"))
      (node (ref "R_S2") (pin "2") (pinfunction "2_2") (pintype "passive"))
      (node (ref "SENSE_OUT") (pin "2") (pinfunction "2_2") (pintype "bidirectional"))
      (node (ref "SHUNT_RES_POS") (pin "1") (pinfunction "P_1") (pintype "passive"))
    )
    (net (code "41") (name "/V_C") (class "Default")
      (node (ref "C6") (pin "2") (pinfunction "2_2") (pintype "passive"))
      (node (ref "R13") (pin "2") (pinfunction "2_2") (pintype "passive"))
      (node (ref "U1") (pin "18") (pinfunction "VC_18") (pintype "passive"))
    )
    (net (code "42") (name "GND") (class "Default")
      (node (ref "ARDUINO_NANO1") (pin "14") (pinfunction "GND_14") (pintype "power_in"))
      (node (ref "ARDUINO_NANO1") (pin "19") (pinfunction "GND_19") (pintype "power_in"))
      (node (ref "BAT_GND") (pin "1") (pinfunction "P_1") (pintype "passive"))
      (node (ref "C1") (pin "1") (pinfunction "1_1") (pintype "passive"))
      (node (ref "C10") (pin "1") (pinfunction "1_1") (pintype "passive"))
      (node (ref "C11") (pin "1") (pinfunction "1_1") (pintype "passive"))
      (node (ref "C13") (pin "2") (pinfunction "2_2") (pintype "passive"))
      (node (ref "C2") (pin "1") (pinfunction "1_1") (pintype "passive"))
      (node (ref "C3") (pin "1") (pinfunction "1_1") (pintype "passive"))
      (node (ref "C4") (pin "1") (pinfunction "1_1") (pintype "passive"))
      (node (ref "C5") (pin "1") (pinfunction "1_1") (pintype "passive"))
      (node (ref "C6") (pin "1") (pinfunction "1_1") (pintype "passive"))
      (node (ref "C7") (pin "1") (pinfunction "1_1") (pintype "passive"))
      (node (ref "C8") (pin "1") (pinfunction "1_1") (pintype "passive"))
      (node (ref "C9") (pin "2") (pinfunction "2_2") (pintype "passive"))
      (node (ref "CURRENT_SENSE") (pin "1") (pinfunction "1_1") (pintype "passive"))
      (node (ref "C_C1") (pin "2") (pinfunction "2_2") (pintype "passive"))
      (node (ref "C_CSPOUT") (pin "2") (pinfunction "2_2") (pintype "bidirectional"))
      (node (ref "C_DACI") (pin "1") (pinfunction "1_1") (pintype "passive"))
      (node (ref "C_DACO") (pin "1") (pinfunction "1_1") (pintype "passive"))
      (node (ref "C_IMON_IN") (pin "1") (pinfunction "1_1") (pintype "passive"))
      (node (ref "C_IMON_OUT") (pin "1") (pinfunction "1_1") (pintype "passive"))
      (node (ref "C_IN1") (pin "2") (pinfunction "-_2") (pintype "bidirectional"))
      (node (ref "C_IN1_2") (pin "2") (pinfunction "-_2") (pintype "bidirectional"))
      (node (ref "C_IN1_3") (pin "2") (pinfunction "-_2") (pintype "bidirectional"))
      (node (ref "C_IN2") (pin "2") (pinfunction "2_2") (pintype "bidirectional"))
      (node (ref "C_IN2_2") (pin "2") (pinfunction "2_2") (pintype "bidirectional"))
      (node (ref "C_IN3") (pin "1") (pinfunction "1_1") (pintype "bidirectional"))
      (node (ref "C_IN3_2") (pin "1") (pinfunction "1_1") (pintype "bidirectional"))
      (node (ref "C_IN4") (pin "2") (pinfunction "2_2") (pintype "bidirectional"))
      (node (ref "C_IN5") (pin "2") (pinfunction "2_2") (pintype "passive"))
      (node (ref "C_OUT1") (pin "2") (pinfunction "-_2") (pintype "bidirectional"))
      (node (ref "C_OUT2") (pin "2") (pinfunction "2_2") (pintype "bidirectional"))
      (node (ref "C_OUT2_2") (pin "2") (pinfunction "2_2") (pintype "bidirectional"))
      (node (ref "C_OUT3") (pin "2") (pinfunction "2_2") (pintype "bidirectional"))
      (node (ref "C_OUT3_2") (pin "2") (pinfunction "2_2") (pintype "bidirectional"))
      (node (ref "C_OUT4") (pin "2") (pinfunction "2_2") (pintype "bidirectional"))
      (node (ref "IC1") (pin "2") (pinfunction "GROUND_2") (pintype "bidirectional"))
      (node (ref "L1") (pin "3") (pinfunction "3_3") (pintype "bidirectional"))
      (node (ref "R18") (pin "1") (pinfunction "1_1") (pintype "passive"))
      (node (ref "R21") (pin "1") (pinfunction "1_1") (pintype "passive"))
      (node (ref "R23") (pin "1") (pinfunction "1_1") (pintype "passive"))
      (node (ref "R4") (pin "2") (pinfunction "2_2") (pintype "passive"))
      (node (ref "R5") (pin "2") (pinfunction "2_2") (pintype "passive"))
      (node (ref "R_DSA") (pin "1") (pinfunction "1_1") (pintype "passive"))
      (node (ref "R_FBIN2") (pin "1") (pinfunction "1_1") (pintype "passive"))
      (node (ref "R_FBOUT2") (pin "2") (pinfunction "2_2") (pintype "passive"))
      (node (ref "R_IMON_IN") (pin "1") (pinfunction "1_1") (pintype "passive"))
      (node (ref "R_IMON_OUT") (pin "1") (pinfunction "1_1") (pintype "passive"))
      (node (ref "SHUNT_NFET") (pin "3") (pinfunction "S_3") (pintype "bidirectional"))
      (node (ref "SOLAR_GND") (pin "1") (pinfunction "P_1") (pintype "passive"))
      (node (ref "TG3") (pin "2") (pinfunction "2_2") (pintype "bidirectional"))
      (node (ref "TG4") (pin "2") (pinfunction "2_2") (pintype "passive"))
      (node (ref "U1") (pin "21") (pinfunction "SYNC_21") (pintype "passive"))
      (node (ref "U1") (pin "55") (pinfunction "GND_55") (pintype "passive"))
      (node (ref "U1") (pin "59") (pinfunction "GND_3_59") (pintype "passive"))
      (node (ref "U1") (pin "62") (pinfunction "GND_2_62") (pintype "passive"))
      (node (ref "U1") (pin "9") (pinfunction "MODE_9") (pintype "passive"))
      (node (ref "U1") (pin "PAD") (pinfunction "EPAD_PAD") (pintype "passive"))
    )
    (net (code "43") (name "Net-(ARDUINO_NANO1-D3)") (class "Default")
      (node (ref "ARDUINO_NANO1") (pin "21") (pinfunction "D3_21") (pintype "bidirectional"))
      (node (ref "SHUNT_NFET") (pin "1") (pinfunction "G_1") (pintype "bidirectional"))
    )
    (net (code "44") (name "Net-(ARDUINO_NANO1-VIN)") (class "Default")
      (node (ref "ARDUINO_NANO1") (pin "15") (pinfunction "VIN_15") (pintype "power_in"))
      (node (ref "C10") (pin "2") (pinfunction "2_2") (pintype "passive"))
      (node (ref "IC1") (pin "3") (pinfunction "OUTPUT_3") (pintype "bidirectional"))
    )
    (net (code "45") (name "Net-(BAT_RES_PAD-P)") (class "Default")
      (node (ref "BAT_RES_PAD") (pin "1") (pinfunction "P_1") (pintype "passive"))
      (node (ref "R_BAT") (pin "2") (pinfunction "2_2") (pintype "passive"))
    )
    (net (code "46") (name "Net-(C7-Pad2)") (class "Default")
      (node (ref "C7") (pin "2") (pinfunction "2_2") (pintype "passive"))
      (node (ref "R13") (pin "1") (pinfunction "1_1") (pintype "passive"))
    )
    (net (code "47") (name "Net-(C_DACI-Pad2)") (class "Default")
      (node (ref "C_DACI") (pin "2") (pinfunction "2_2") (pintype "passive"))
      (node (ref "R_DACI1") (pin "1") (pinfunction "1_1") (pintype "passive"))
      (node (ref "R_DACI2") (pin "2") (pinfunction "2_2") (pintype "passive"))
    )
    (net (code "48") (name "Net-(C_DACO-Pad2)") (class "Default")
      (node (ref "C_DACO") (pin "2") (pinfunction "2_2") (pintype "passive"))
      (node (ref "R_DACO1") (pin "1") (pinfunction "1_1") (pintype "passive"))
      (node (ref "R_DACO2") (pin "2") (pinfunction "2_2") (pintype "passive"))
    )
    (net (code "49") (name "Net-(D_S-PadC)") (class "Default")
      (node (ref "D_S") (pin "C") (pinfunction "C_C") (pintype "passive"))
      (node (ref "R_DSA") (pin "2") (pinfunction "2_2") (pintype "passive"))
    )
    (net (code "50") (name "Net-(M1-D_1)") (class "Default")
      (node (ref "C_IN3") (pin "2") (pinfunction "2_2") (pintype "bidirectional"))
      (node (ref "C_IN3_2") (pin "2") (pinfunction "2_2") (pintype "bidirectional"))
      (node (ref "M1") (pin "5") (pinfunction "D_1_5") (pintype "bidirectional"))
      (node (ref "M1") (pin "6") (pinfunction "D_2_6") (pintype "bidirectional"))
      (node (ref "M1") (pin "7") (pinfunction "D_3_7") (pintype "bidirectional"))
      (node (ref "M1") (pin "8") (pinfunction "D_4_8") (pintype "bidirectional"))
      (node (ref "M1") (pin "9") (pinfunction "D_5_9") (pintype "bidirectional"))
      (node (ref "R_S1") (pin "1") (pinfunction "1_1") (pintype "passive"))
      (node (ref "SENSE_IN") (pin "1") (pinfunction "1_1") (pintype "bidirectional"))
    )
    (net (code "51") (name "Net-(M1-G)") (class "Default")
      (node (ref "M1") (pin "4") (pinfunction "G_4") (pintype "bidirectional"))
      (node (ref "TG1") (pin "1") (pinfunction "1_1") (pintype "passive"))
    )
    (net (code "52") (name "Net-(M2-S_1)") (class "Default")
      (node (ref "M2") (pin "1") (pinfunction "S_1_1") (pintype "bidirectional"))
      (node (ref "M2") (pin "2") (pinfunction "S_2_2") (pintype "bidirectional"))
      (node (ref "M2") (pin "3") (pinfunction "S_3_3") (pintype "bidirectional"))
      (node (ref "M3") (pin "1") (pinfunction "S_1_1") (pintype "bidirectional"))
      (node (ref "M3") (pin "2") (pinfunction "S_2_2") (pintype "bidirectional"))
      (node (ref "M3") (pin "3") (pinfunction "S_3_3") (pintype "bidirectional"))
      (node (ref "TG2") (pin "2") (pinfunction "2_2") (pintype "passive"))
      (node (ref "TG3") (pin "1") (pinfunction "1_1") (pintype "bidirectional"))
    )
    (net (code "53") (name "Net-(M3-G)") (class "Default")
      (node (ref "M3") (pin "4") (pinfunction "G_4") (pintype "bidirectional"))
      (node (ref "TG5") (pin "1") (pinfunction "1_1") (pintype "passive"))
    )
    (net (code "54") (name "Net-(SHUNT_NFET-D)") (class "Default")
      (node (ref "SHUNT_NFET") (pin "2") (pinfunction "D_2") (pintype "bidirectional"))
      (node (ref "SHUNT_RES_NEG") (pin "1") (pinfunction "P_1") (pintype "passive"))
    )
    (net (code "55") (name "unconnected-(ARDUINO_NANO1-3V3-Pad2)") (class "Default")
      (node (ref "ARDUINO_NANO1") (pin "2") (pinfunction "3V3_2") (pintype "output"))
    )
    (net (code "56") (name "unconnected-(ARDUINO_NANO1-A1-Pad5)") (class "Default")
      (node (ref "ARDUINO_NANO1") (pin "5") (pinfunction "A1_5") (pintype "bidirectional"))
    )
    (net (code "57") (name "unconnected-(ARDUINO_NANO1-A2-Pad6)") (class "Default")
      (node (ref "ARDUINO_NANO1") (pin "6") (pinfunction "A2_6") (pintype "bidirectional"))
    )
    (net (code "58") (name "unconnected-(ARDUINO_NANO1-A3-Pad7)") (class "Default")
      (node (ref "ARDUINO_NANO1") (pin "7") (pinfunction "A3_7") (pintype "bidirectional"))
    )
    (net (code "59") (name "unconnected-(ARDUINO_NANO1-A6-Pad10)") (class "Default")
      (node (ref "ARDUINO_NANO1") (pin "10") (pinfunction "A6_10") (pintype "bidirectional"))
    )
    (net (code "60") (name "unconnected-(ARDUINO_NANO1-A7-Pad11)") (class "Default")
      (node (ref "ARDUINO_NANO1") (pin "11") (pinfunction "A7_11") (pintype "bidirectional"))
    )
    (net (code "61") (name "unconnected-(ARDUINO_NANO1-AREF-Pad3)") (class "Default")
      (node (ref "ARDUINO_NANO1") (pin "3") (pinfunction "AREF_3") (pintype "input"))
    )
    (net (code "62") (name "unconnected-(ARDUINO_NANO1-D2-Pad20)") (class "Default")
      (node (ref "ARDUINO_NANO1") (pin "20") (pinfunction "D2_20") (pintype "bidirectional"))
    )
    (net (code "63") (name "unconnected-(ARDUINO_NANO1-D4-Pad22)") (class "Default")
      (node (ref "ARDUINO_NANO1") (pin "22") (pinfunction "D4_22") (pintype "bidirectional"))
    )
    (net (code "64") (name "unconnected-(ARDUINO_NANO1-D5-Pad23)") (class "Default")
      (node (ref "ARDUINO_NANO1") (pin "23") (pinfunction "D5_23") (pintype "bidirectional"))
    )
    (net (code "65") (name "unconnected-(ARDUINO_NANO1-D6-Pad24)") (class "Default")
      (node (ref "ARDUINO_NANO1") (pin "24") (pinfunction "D6_24") (pintype "bidirectional"))
    )
    (net (code "66") (name "unconnected-(ARDUINO_NANO1-D7-Pad25)") (class "Default")
      (node (ref "ARDUINO_NANO1") (pin "25") (pinfunction "D7_25") (pintype "bidirectional"))
    )
    (net (code "67") (name "unconnected-(ARDUINO_NANO1-D8-Pad26)") (class "Default")
      (node (ref "ARDUINO_NANO1") (pin "26") (pinfunction "D8_26") (pintype "bidirectional"))
    )
    (net (code "68") (name "unconnected-(ARDUINO_NANO1-D9-Pad27)") (class "Default")
      (node (ref "ARDUINO_NANO1") (pin "27") (pinfunction "D9_27") (pintype "bidirectional"))
    )
    (net (code "69") (name "unconnected-(ARDUINO_NANO1-D10-Pad28)") (class "Default")
      (node (ref "ARDUINO_NANO1") (pin "28") (pinfunction "D10_28") (pintype "bidirectional"))
    )
    (net (code "70") (name "unconnected-(ARDUINO_NANO1-D11-Pad29)") (class "Default")
      (node (ref "ARDUINO_NANO1") (pin "29") (pinfunction "D11_29") (pintype "bidirectional"))
    )
    (net (code "71") (name "unconnected-(ARDUINO_NANO1-D12-Pad30)") (class "Default")
      (node (ref "ARDUINO_NANO1") (pin "30") (pinfunction "D12_30") (pintype "bidirectional"))
    )
    (net (code "72") (name "unconnected-(ARDUINO_NANO1-D13-Pad1)") (class "Default")
      (node (ref "ARDUINO_NANO1") (pin "1") (pinfunction "D13_1") (pintype "bidirectional"))
    )
    (net (code "73") (name "unconnected-(ARDUINO_NANO1-RX0-Pad17)") (class "Default")
      (node (ref "ARDUINO_NANO1") (pin "17") (pinfunction "RX0_17") (pintype "bidirectional"))
    )
    (net (code "74") (name "unconnected-(ARDUINO_NANO1-TX1-Pad16)") (class "Default")
      (node (ref "ARDUINO_NANO1") (pin "16") (pinfunction "TX1_16") (pintype "bidirectional"))
    )
    (net (code "75") (name "unconnected-(ARDUINO_NANO1-~{RESET}-Pad13)") (class "Default")
      (node (ref "ARDUINO_NANO1") (pin "13") (pinfunction "~{RESET}_13") (pintype "input"))
    )
    (net (code "76") (name "unconnected-(ARDUINO_NANO1-~{RESET}-Pad18)") (class "Default")
      (node (ref "ARDUINO_NANO1") (pin "18") (pinfunction "~{RESET}_18") (pintype "input"))
    )
    (net (code "77") (name "unconnected-(U1-ECON-Pad48)") (class "Default")
      (node (ref "U1") (pin "48") (pinfunction "ECON_48") (pintype "passive"))
    )
    (net (code "78") (name "unconnected-(U1-NC-Pad60)") (class "Default")
      (node (ref "U1") (pin "60") (pinfunction "NC_60") (pintype "passive"))
    )
    (net (code "79") (name "unconnected-(U1-NC_2-Pad52)") (class "Default")
      (node (ref "U1") (pin "52") (pinfunction "NC_2_52") (pintype "passive"))
    )
    (net (code "80") (name "unconnected-(U1-SRVO_FBIN-Pad35)") (class "Default")
      (node (ref "U1") (pin "35") (pinfunction "SRVO_FBIN_35") (pintype "passive"))
    )
    (net (code "81") (name "unconnected-(U1-SRVO_FBOUT-Pad38)") (class "Default")
      (node (ref "U1") (pin "38") (pinfunction "SRVO_FBOUT_38") (pintype "passive"))
    )
    (net (code "82") (name "unconnected-(U1-SRVO_IIN-Pad36)") (class "Default")
      (node (ref "U1") (pin "36") (pinfunction "SRVO_IIN_36") (pintype "passive"))
    )
    (net (code "83") (name "unconnected-(U1-SRVO_IOUT-Pad37)") (class "Default")
      (node (ref "U1") (pin "37") (pinfunction "SRVO_IOUT_37") (pintype "passive"))
    )
  )
)
